# 05_MCU.net
KiCad netlist of a schematic drawn in Altium Designer
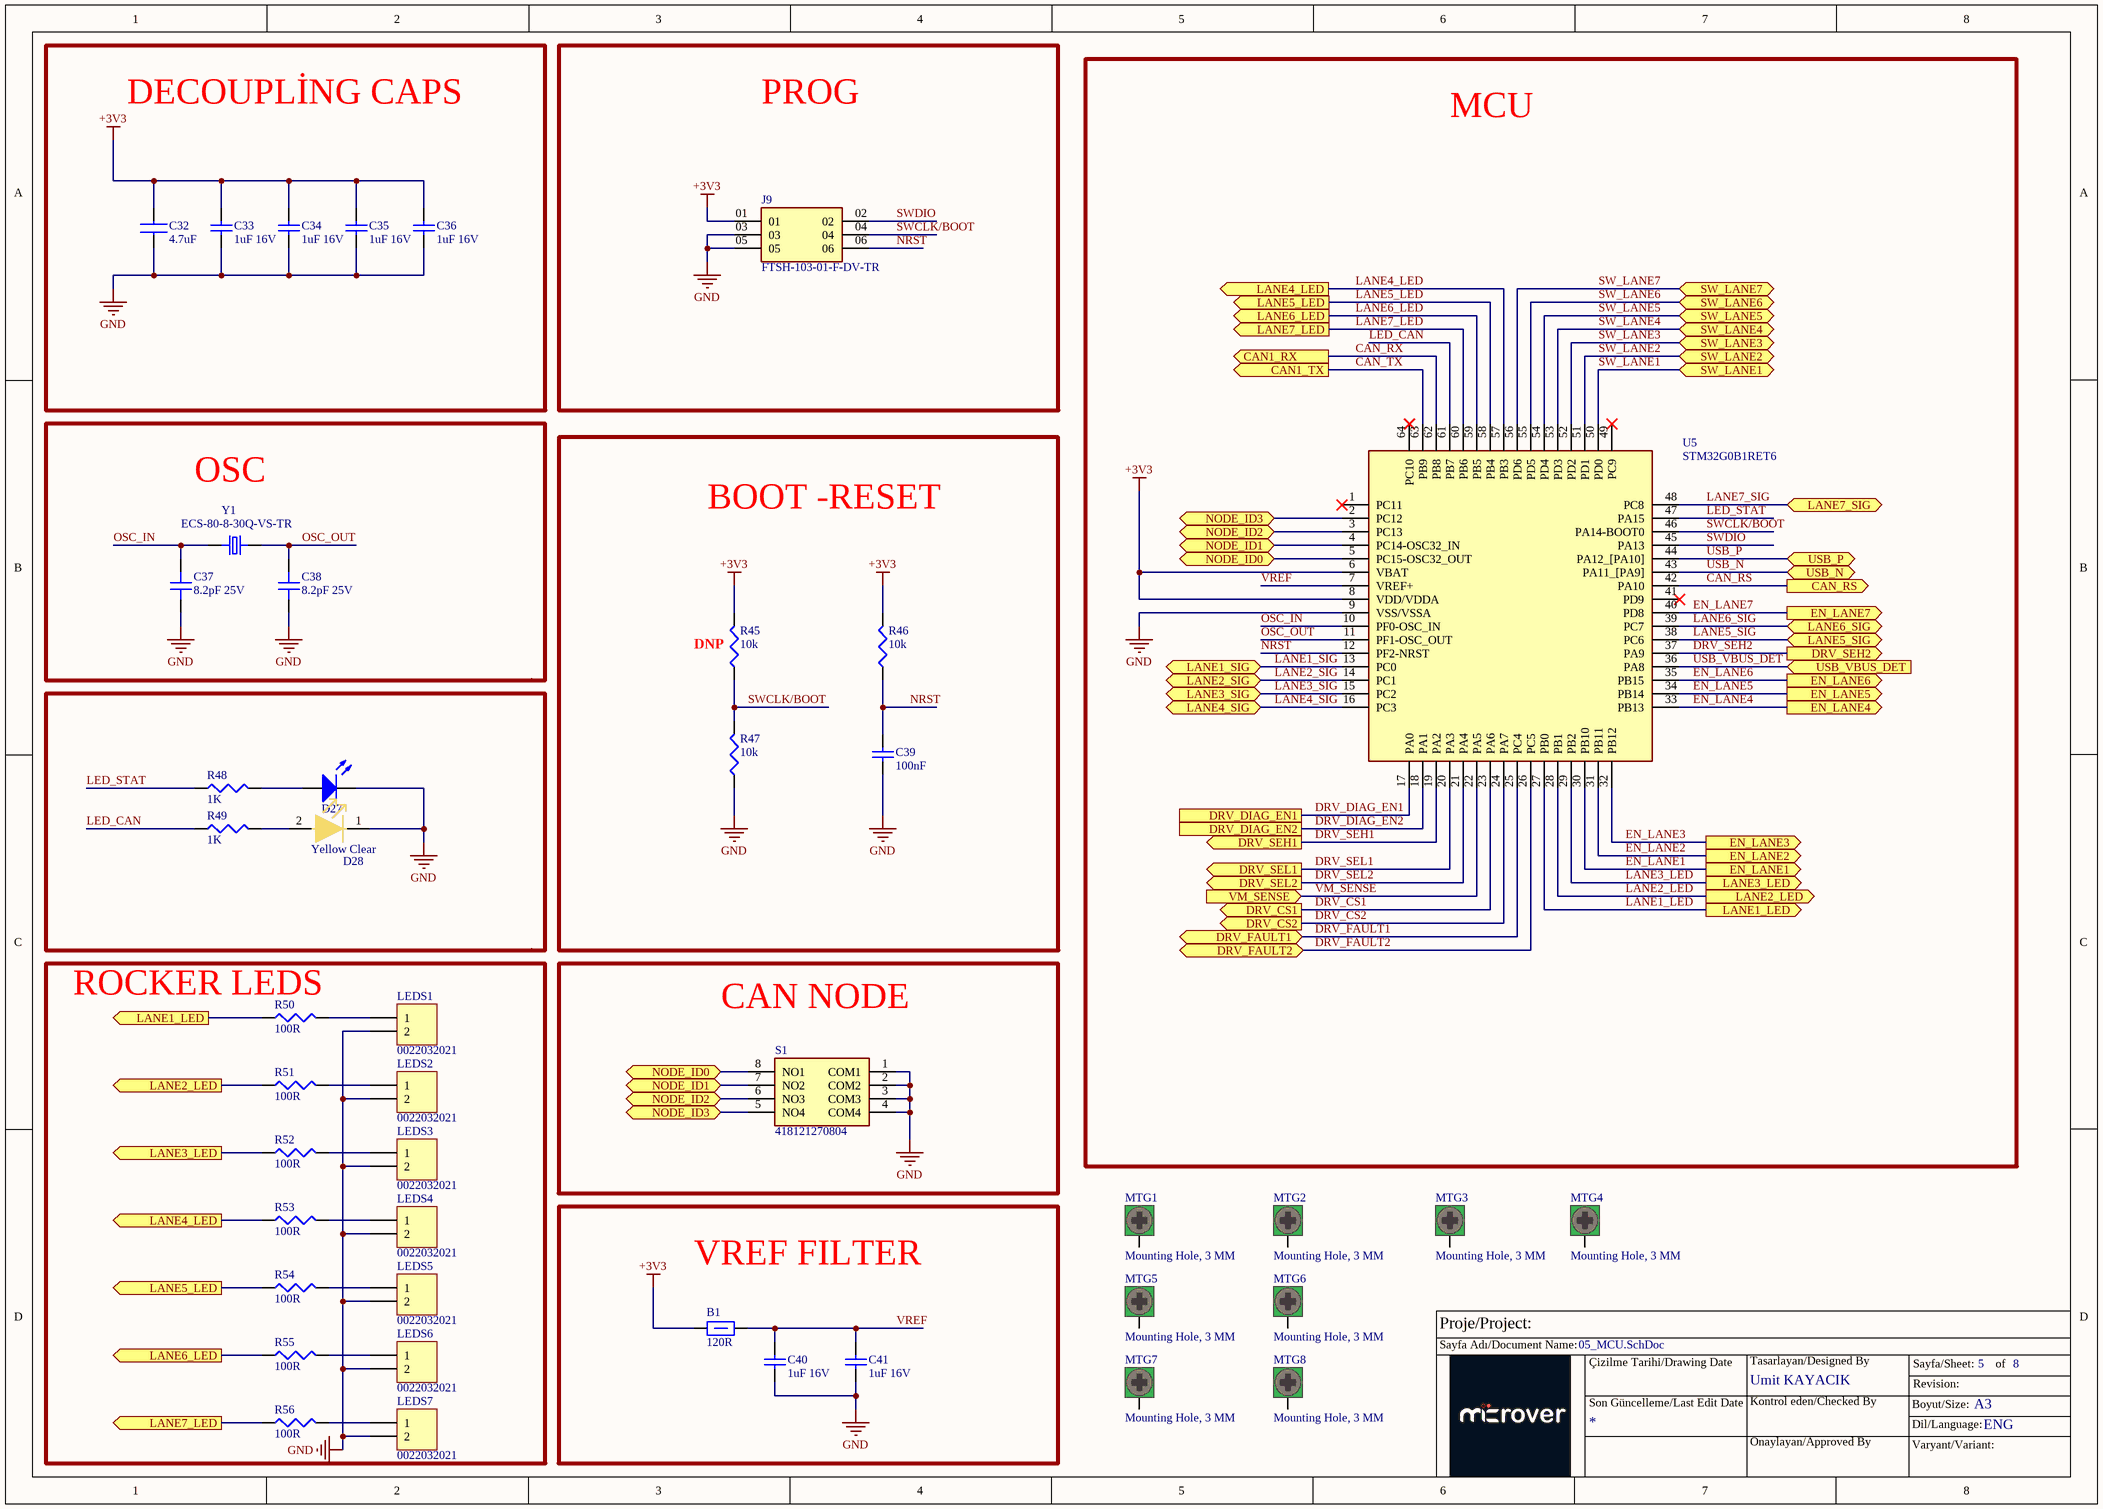
[diagram p0: 05_MCU.SchDoc]

(export (version "E")
  (design (tool "Eeschema 10.0.6"))
  (components
    (comp (ref "B1")
      (value "120R")
      (footprint "F0603")
      (description "BEAD FERRITE 120R 1LN SMD 0603")
      (fields (field (name "MANUFACTURER") "MURATA"))
      (libsource (lib "HW_ADHERENT_LANECTRL_R1") (part "BEAD FERRITE 120R 1LN SMD 0603"))
    )
    (comp (ref "C32")
      (value "4.7uF")
      (footprint "CAP0603")
      (description "4.7 µF ±20% 10V Ceramic Capacitor X5R 0603 (1608 Metric)")
      (fields (field (name "MANUFACTURER PART NUMBER") "GRM185R61A475ME11D"))
      (libsource (lib "HW_ADHERENT_LANECTRL_R1") (part "CAP0603_4.7uF_10V"))
    )
    (comp (ref "C33")
      (value "1uF 16V")
      (footprint "SMC0603")
      (description "1 µF ±10% 16V Ceramic Capacitor X7R 0603 (1608 Metric)")
      (fields
        (field (name "MANUFACTURER PART NUMBER") "CGA3E1X7R1C105K080AC")
        (field (name "Comment") "CAP CER 1UF 16V X7R 0603")
      )
      (libsource (lib "HW_ADHERENT_LANECTRL_R1") (part "CAP0603_1UF_16V"))
    )
    (comp (ref "C34")
      (value "1uF 16V")
      (footprint "SMC0603")
      (description "1 µF ±10% 16V Ceramic Capacitor X7R 0603 (1608 Metric)")
      (fields
        (field (name "MANUFACTURER PART NUMBER") "CGA3E1X7R1C105K080AC")
        (field (name "Comment") "CAP CER 1UF 16V X7R 0603")
      )
      (libsource (lib "HW_ADHERENT_LANECTRL_R1") (part "CAP0603_1UF_16V"))
    )
    (comp (ref "C35")
      (value "1uF 16V")
      (footprint "SMC0603")
      (description "1 µF ±10% 16V Ceramic Capacitor X7R 0603 (1608 Metric)")
      (fields
        (field (name "MANUFACTURER PART NUMBER") "CGA3E1X7R1C105K080AC")
        (field (name "Comment") "CAP CER 1UF 16V X7R 0603")
      )
      (libsource (lib "HW_ADHERENT_LANECTRL_R1") (part "CAP0603_1UF_16V"))
    )
    (comp (ref "C36")
      (value "1uF 16V")
      (footprint "SMC0603")
      (description "1 µF ±10% 16V Ceramic Capacitor X7R 0603 (1608 Metric)")
      (fields
        (field (name "MANUFACTURER PART NUMBER") "CGA3E1X7R1C105K080AC")
        (field (name "Comment") "CAP CER 1UF 16V X7R 0603")
      )
      (libsource (lib "HW_ADHERENT_LANECTRL_R1") (part "CAP0603_1UF_16V"))
    )
    (comp (ref "C37")
      (value "8.2pF 25V")
      (footprint "0402_C")
      (description "CAP0402 COG 8.2PF 5% 25V")
      (libsource (lib "HW_ADHERENT_LANECTRL_R1") (part "GMC04CG8R2J25NT"))
    )
    (comp (ref "C38")
      (value "8.2pF 25V")
      (footprint "0402_C")
      (description "CAP0402 COG 8.2PF 5% 25V")
      (libsource (lib "HW_ADHERENT_LANECTRL_R1") (part "GMC04CG8R2J25NT"))
    )
    (comp (ref "C39")
      (value "100nF")
      (footprint "CAP0603")
      (description "0.1 µF ±10% 50V Ceramic Capacitor X7R 0603 (1608 Metric)")
      (fields
        (field (name "MANUFACTURER PART NUMBER") "CL10B104KA8NNNC")
        (field (name "LCSC PART NUMBER") "C1590")
      )
      (libsource (lib "HW_ADHERENT_LANECTRL_R1") (part "CAP0603_100nF"))
    )
    (comp (ref "C40")
      (value "1uF 16V")
      (footprint "SMC0603")
      (description "1 µF ±10% 16V Ceramic Capacitor X7R 0603 (1608 Metric)")
      (fields
        (field (name "MANUFACTURER PART NUMBER") "CGA3E1X7R1C105K080AC")
        (field (name "Comment") "CAP CER 1UF 16V X7R 0603")
      )
      (libsource (lib "HW_ADHERENT_LANECTRL_R1") (part "CAP0603_1UF_16V"))
    )
    (comp (ref "C41")
      (value "1uF 16V")
      (footprint "SMC0603")
      (description "1 µF ±10% 16V Ceramic Capacitor X7R 0603 (1608 Metric)")
      (fields
        (field (name "MANUFACTURER PART NUMBER") "CGA3E1X7R1C105K080AC")
        (field (name "Comment") "CAP CER 1UF 16V X7R 0603")
      )
      (libsource (lib "HW_ADHERENT_LANECTRL_R1") (part "CAP0603_1UF_16V"))
    )
    (comp (ref "D27")
      (value "LED GREEN")
      (footprint "LED0805")
      (description "Green 570nm LED Indication - Discrete 2.1V 0805 (2012 Metric)")
      (fields
        (field (name "MANUFACTURER PART NUMBER") "QTLP630C4TR")
        (field (name "MANUFACTURER") "Everlight Electronics Co Ltd")
      )
      (libsource (lib "HW_ADHERENT_LANECTRL_R1") (part "LED0805_GREEN"))
    )
    (comp (ref "D28")
      (value "LED YELLOW CLEAR SMD")
      (footprint "Lite-On_Yellow_0603")
      (description "Yellow 591nm LED Indication - Discrete 2.1V 0603 (1608 Metric)")
      (fields (field (name "MANUFACTURER PART NUMBER") "LTST-C191KSKT") (field (name "COLOR") "Yellow Clear"))
      (libsource (lib "HW_ADHERENT_LANECTRL_R1") (part "LTST-C191KSKT"))
    )
    (comp (ref "J9")
      (value "FTSH-103-01-F-DV-TR")
      (footprint "SAMTEC_FTSH-103-01-F-DV-TR")
      (description "Connector Header Surface Mount 6 position 0.050\" (1.27mm)")
      (fields (field (name "MANUFACTURER") "Samtec Inc."))
      (libsource (lib "HW_ADHERENT_LANECTRL_R1") (part "FTSH-103-01-F-DV-TR"))
    )
    (comp (ref "LEDS1")
      (value "0022032021")
      (footprint "THD 1x2p. male straight")
      (description "CONN HEADER VERT 2POS 2.54MM")
      (fields (field (name "MANUFACTURER") "Molex"))
      (libsource (lib "HW_ADHERENT_LANECTRL_R1") (part "Header 2"))
    )
    (comp (ref "LEDS2")
      (value "0022032021")
      (footprint "THD 1x2p. male straight")
      (description "CONN HEADER VERT 2POS 2.54MM")
      (fields (field (name "MANUFACTURER") "Molex"))
      (libsource (lib "HW_ADHERENT_LANECTRL_R1") (part "Header 2"))
    )
    (comp (ref "LEDS3")
      (value "0022032021")
      (footprint "THD 1x2p. male straight")
      (description "CONN HEADER VERT 2POS 2.54MM")
      (fields (field (name "MANUFACTURER") "Molex"))
      (libsource (lib "HW_ADHERENT_LANECTRL_R1") (part "Header 2"))
    )
    (comp (ref "LEDS4")
      (value "0022032021")
      (footprint "THD 1x2p. male straight")
      (description "CONN HEADER VERT 2POS 2.54MM")
      (fields (field (name "MANUFACTURER") "Molex"))
      (libsource (lib "HW_ADHERENT_LANECTRL_R1") (part "Header 2"))
    )
    (comp (ref "LEDS5")
      (value "0022032021")
      (footprint "THD 1x2p. male straight")
      (description "CONN HEADER VERT 2POS 2.54MM")
      (fields (field (name "MANUFACTURER") "Molex"))
      (libsource (lib "HW_ADHERENT_LANECTRL_R1") (part "Header 2"))
    )
    (comp (ref "LEDS6")
      (value "0022032021")
      (footprint "THD 1x2p. male straight")
      (description "CONN HEADER VERT 2POS 2.54MM")
      (fields (field (name "MANUFACTURER") "Molex"))
      (libsource (lib "HW_ADHERENT_LANECTRL_R1") (part "Header 2"))
    )
    (comp (ref "LEDS7")
      (value "0022032021")
      (footprint "THD 1x2p. male straight")
      (description "CONN HEADER VERT 2POS 2.54MM")
      (fields (field (name "MANUFACTURER") "Molex"))
      (libsource (lib "HW_ADHERENT_LANECTRL_R1") (part "Header 2"))
    )
    (comp (ref "MTG1")
      (value "Mounting Hole, 3 MM")
      (footprint "M3 Mounting Hole")
      (libsource (lib "HW_ADHERENT_LANECTRL_R1") (part "MTG3MM_8"))
    )
    (comp (ref "MTG2")
      (value "Mounting Hole, 3 MM")
      (footprint "M3 Mounting Hole")
      (libsource (lib "HW_ADHERENT_LANECTRL_R1") (part "MTG3MM_8"))
    )
    (comp (ref "MTG3")
      (value "Mounting Hole, 3 MM")
      (footprint "M3 Mounting Hole")
      (libsource (lib "HW_ADHERENT_LANECTRL_R1") (part "MTG3MM_8"))
    )
    (comp (ref "MTG4")
      (value "Mounting Hole, 3 MM")
      (footprint "M3 Mounting Hole")
      (libsource (lib "HW_ADHERENT_LANECTRL_R1") (part "MTG3MM_8"))
    )
    (comp (ref "MTG5")
      (value "Mounting Hole, 3 MM")
      (footprint "M3 Mounting Hole")
      (libsource (lib "HW_ADHERENT_LANECTRL_R1") (part "MTG3MM_8"))
    )
    (comp (ref "MTG6")
      (value "Mounting Hole, 3 MM")
      (footprint "M3 Mounting Hole")
      (libsource (lib "HW_ADHERENT_LANECTRL_R1") (part "MTG3MM_8"))
    )
    (comp (ref "MTG7")
      (value "Mounting Hole, 3 MM")
      (footprint "M3 Mounting Hole")
      (libsource (lib "HW_ADHERENT_LANECTRL_R1") (part "MTG3MM_8"))
    )
    (comp (ref "MTG8")
      (value "Mounting Hole, 3 MM")
      (footprint "M3 Mounting Hole")
      (libsource (lib "HW_ADHERENT_LANECTRL_R1") (part "MTG3MM_8"))
    )
    (comp (ref "R45")
      (value "10k")
      (footprint "SMR0603")
      (description "10 kOhms ±1% 0.1W, 1/10W Chip Resistor 0603 (1608 Metric) Moisture Resistant Thick Film")
      (fields
        (field (name "MANUFACTURER PART NUMBER") "RC0603FR-0710KL")
        (field (name "LCSC PART NUMBER") "C98220")
      )
      (libsource (lib "HW_ADHERENT_LANECTRL_R1") (part "RES0603_10K_%1"))
    )
    (comp (ref "R46")
      (value "10k")
      (footprint "SMR0603")
      (description "10 kOhms ±1% 0.1W, 1/10W Chip Resistor 0603 (1608 Metric) Moisture Resistant Thick Film")
      (fields
        (field (name "MANUFACTURER PART NUMBER") "RC0603FR-0710KL")
        (field (name "LCSC PART NUMBER") "C98220")
      )
      (libsource (lib "HW_ADHERENT_LANECTRL_R1") (part "RES0603_10K_%1"))
    )
    (comp (ref "R47")
      (value "10k")
      (footprint "SMR0603")
      (description "10 kOhms ±1% 0.1W, 1/10W Chip Resistor 0603 (1608 Metric) Moisture Resistant Thick Film")
      (fields
        (field (name "MANUFACTURER PART NUMBER") "RC0603FR-0710KL")
        (field (name "LCSC PART NUMBER") "C98220")
      )
      (libsource (lib "HW_ADHERENT_LANECTRL_R1") (part "RES0603_10K_%1"))
    )
    (comp (ref "R48")
      (value "1K")
      (footprint "R 0603(1608)")
      (description "RES SMD 1K OHM 1% 1/10W 0603")
      (fields
        (field (name "MANUFACTURER") "Yageo")
        (field (name "MANUFACTURER PART NUMBER") "RC0603FR-071KL")
      )
      (libsource (lib "HW_ADHERENT_LANECTRL_R1") (part "Res3_9"))
    )
    (comp (ref "R49")
      (value "1K")
      (footprint "R 0603(1608)")
      (description "RES SMD 1K OHM 1% 1/10W 0603")
      (fields
        (field (name "MANUFACTURER") "Yageo")
        (field (name "MANUFACTURER PART NUMBER") "RC0603FR-071KL")
      )
      (libsource (lib "HW_ADHERENT_LANECTRL_R1") (part "Res3_9"))
    )
    (comp (ref "R50")
      (value "100R")
      (footprint "SMR0603")
      (description "100 Ohms ±1% 0.1W, 1/10W Chip Resistor 0603 (1608 Metric) Moisture Resistant Thick Film")
      (fields
        (field (name "MANUFACTURER PART NUMBER") "RC0603FR-07100RL")
        (field (name "LCSC PART NUMBER") "C105588")
      )
      (libsource (lib "HW_ADHERENT_LANECTRL_R1") (part "RES0603_100R_%1_1"))
    )
    (comp (ref "R51")
      (value "100R")
      (footprint "SMR0603")
      (description "100 Ohms ±1% 0.1W, 1/10W Chip Resistor 0603 (1608 Metric) Moisture Resistant Thick Film")
      (fields
        (field (name "MANUFACTURER PART NUMBER") "RC0603FR-07100RL")
        (field (name "LCSC PART NUMBER") "C105588")
      )
      (libsource (lib "HW_ADHERENT_LANECTRL_R1") (part "RES0603_100R_%1_1"))
    )
    (comp (ref "R52")
      (value "100R")
      (footprint "SMR0603")
      (description "100 Ohms ±1% 0.1W, 1/10W Chip Resistor 0603 (1608 Metric) Moisture Resistant Thick Film")
      (fields
        (field (name "MANUFACTURER PART NUMBER") "RC0603FR-07100RL")
        (field (name "LCSC PART NUMBER") "C105588")
      )
      (libsource (lib "HW_ADHERENT_LANECTRL_R1") (part "RES0603_100R_%1_1"))
    )
    (comp (ref "R53")
      (value "100R")
      (footprint "SMR0603")
      (description "100 Ohms ±1% 0.1W, 1/10W Chip Resistor 0603 (1608 Metric) Moisture Resistant Thick Film")
      (fields
        (field (name "MANUFACTURER PART NUMBER") "RC0603FR-07100RL")
        (field (name "LCSC PART NUMBER") "C105588")
      )
      (libsource (lib "HW_ADHERENT_LANECTRL_R1") (part "RES0603_100R_%1_1"))
    )
    (comp (ref "R54")
      (value "100R")
      (footprint "SMR0603")
      (description "100 Ohms ±1% 0.1W, 1/10W Chip Resistor 0603 (1608 Metric) Moisture Resistant Thick Film")
      (fields
        (field (name "MANUFACTURER PART NUMBER") "RC0603FR-07100RL")
        (field (name "LCSC PART NUMBER") "C105588")
      )
      (libsource (lib "HW_ADHERENT_LANECTRL_R1") (part "RES0603_100R_%1_1"))
    )
    (comp (ref "R55")
      (value "100R")
      (footprint "SMR0603")
      (description "100 Ohms ±1% 0.1W, 1/10W Chip Resistor 0603 (1608 Metric) Moisture Resistant Thick Film")
      (fields
        (field (name "MANUFACTURER PART NUMBER") "RC0603FR-07100RL")
        (field (name "LCSC PART NUMBER") "C105588")
      )
      (libsource (lib "HW_ADHERENT_LANECTRL_R1") (part "RES0603_100R_%1_1"))
    )
    (comp (ref "R56")
      (value "100R")
      (footprint "SMR0603")
      (description "100 Ohms ±1% 0.1W, 1/10W Chip Resistor 0603 (1608 Metric) Moisture Resistant Thick Film")
      (fields
        (field (name "MANUFACTURER PART NUMBER") "RC0603FR-07100RL")
        (field (name "LCSC PART NUMBER") "C105588")
      )
      (libsource (lib "HW_ADHERENT_LANECTRL_R1") (part "RES0603_100R_%1_1"))
    )
    (comp (ref "S1")
      (value "418121270804")
      (footprint "418121270804")
      (description "Dip Switch, 0.025A, 24Vdc, 4 Pos, Smd Rohs Compliant: Yes ¦Wurth Elektronik 418121270804")
      (fields (field (name "MANUFACTURER") "Wurth Electronics"))
      (libsource (lib "HW_ADHERENT_LANECTRL_R1") (part "418121270804"))
    )
    (comp (ref "U5")
      (value "STM32G0B1RET6")
      (footprint "QFP50P1200X1200X160-64N")
      (description "ARM® Cortex®-M0+ STM32G0 Microcontroller IC 32-Bit 64MHz 512KB (512K x 8) FLASH 64-LQFP (10x10)")
      (libsource (lib "HW_ADHERENT_LANECTRL_R1") (part "STM32G0B1RET6"))
    )
    (comp (ref "Y1")
      (value "ECS-80-8-30Q-VS-TR")
      (footprint "XTAL_ECS-80-8-30Q-VS-TR")
      (description "CRYSTAL 8.0000MHZ 8PF SMD")
      (fields (field (name "MANUFACTURER") "ESC Inc."))
      (libsource (lib "HW_ADHERENT_LANECTRL_R1") (part "ECS-80-8-30Q-VS-TR"))
    )
  )
  (nets
    (net (code "1") (name "+3V3") (class "Default")
      (node (ref "B1") (pin "1") (pinfunction "1_1") (pintype "passive"))
      (node (ref "C32") (pin "2") (pinfunction "2_2") (pintype "passive"))
      (node (ref "C33") (pin "2") (pinfunction "2_2") (pintype "passive"))
      (node (ref "C34") (pin "2") (pinfunction "2_2") (pintype "passive"))
      (node (ref "C35") (pin "2") (pinfunction "2_2") (pintype "passive"))
      (node (ref "C36") (pin "2") (pinfunction "2_2") (pintype "passive"))
      (node (ref "J9") (pin "01") (pinfunction "01_01") (pintype "passive"))
      (node (ref "R45") (pin "2") (pinfunction "2_2") (pintype "passive"))
      (node (ref "R46") (pin "2") (pinfunction "2_2") (pintype "passive"))
      (node (ref "U5") (pin "6") (pinfunction "VBAT_6") (pintype "passive"))
      (node (ref "U5") (pin "8") (pinfunction "VDD/VDDA_8") (pintype "passive"))
    )
    (net (code "2") (name "/CAN_RS") (class "Default")
      (node (ref "U5") (pin "42") (pinfunction "PA10_42") (pintype "passive"))
    )
    (net (code "3") (name "/CAN_RX") (class "Default")
      (node (ref "U5") (pin "62") (pinfunction "PB8_62") (pintype "passive"))
    )
    (net (code "4") (name "/CAN_TX") (class "Default")
      (node (ref "U5") (pin "63") (pinfunction "PB9_63") (pintype "passive"))
    )
    (net (code "5") (name "/DRV_CS1") (class "Default")
      (node (ref "U5") (pin "23") (pinfunction "PA6_23") (pintype "passive"))
    )
    (net (code "6") (name "/DRV_CS2") (class "Default")
      (node (ref "U5") (pin "24") (pinfunction "PA7_24") (pintype "passive"))
    )
    (net (code "7") (name "/DRV_DIAG_EN1") (class "Default")
      (node (ref "U5") (pin "17") (pinfunction "PA0_17") (pintype "passive"))
    )
    (net (code "8") (name "/DRV_DIAG_EN2") (class "Default")
      (node (ref "U5") (pin "18") (pinfunction "PA1_18") (pintype "passive"))
    )
    (net (code "9") (name "/DRV_FAULT1") (class "Default")
      (node (ref "U5") (pin "25") (pinfunction "PC4_25") (pintype "passive"))
    )
    (net (code "10") (name "/DRV_FAULT2") (class "Default")
      (node (ref "U5") (pin "26") (pinfunction "PC5_26") (pintype "passive"))
    )
    (net (code "11") (name "/DRV_SEH1") (class "Default")
      (node (ref "U5") (pin "19") (pinfunction "PA2_19") (pintype "passive"))
    )
    (net (code "12") (name "/DRV_SEH2") (class "Default")
      (node (ref "U5") (pin "37") (pinfunction "PA9_37") (pintype "passive"))
    )
    (net (code "13") (name "/DRV_SEL1") (class "Default")
      (node (ref "U5") (pin "20") (pinfunction "PA3_20") (pintype "passive"))
    )
    (net (code "14") (name "/DRV_SEL2") (class "Default")
      (node (ref "U5") (pin "21") (pinfunction "PA4_21") (pintype "passive"))
    )
    (net (code "15") (name "/EN_LANE1") (class "Default")
      (node (ref "U5") (pin "30") (pinfunction "PB10_30") (pintype "passive"))
    )
    (net (code "16") (name "/EN_LANE2") (class "Default")
      (node (ref "U5") (pin "31") (pinfunction "PB11_31") (pintype "passive"))
    )
    (net (code "17") (name "/EN_LANE3") (class "Default")
      (node (ref "U5") (pin "32") (pinfunction "PB12_32") (pintype "passive"))
    )
    (net (code "18") (name "/EN_LANE4") (class "Default")
      (node (ref "U5") (pin "33") (pinfunction "PB13_33") (pintype "passive"))
    )
    (net (code "19") (name "/EN_LANE5") (class "Default")
      (node (ref "U5") (pin "34") (pinfunction "PB14_34") (pintype "passive"))
    )
    (net (code "20") (name "/EN_LANE6") (class "Default")
      (node (ref "U5") (pin "35") (pinfunction "PB15_35") (pintype "passive"))
    )
    (net (code "21") (name "/EN_LANE7") (class "Default")
      (node (ref "U5") (pin "40") (pinfunction "PD8_40") (pintype "passive"))
    )
    (net (code "22") (name "/LANE1_LED") (class "Default")
      (node (ref "R50") (pin "1") (pinfunction "1_1") (pintype "passive"))
      (node (ref "U5") (pin "27") (pinfunction "PB0_27") (pintype "passive"))
    )
    (net (code "23") (name "/LANE1_SIG") (class "Default")
      (node (ref "U5") (pin "13") (pinfunction "PC0_13") (pintype "passive"))
    )
    (net (code "24") (name "/LANE2_LED") (class "Default")
      (node (ref "R51") (pin "1") (pinfunction "1_1") (pintype "passive"))
      (node (ref "U5") (pin "28") (pinfunction "PB1_28") (pintype "passive"))
    )
    (net (code "25") (name "/LANE2_SIG") (class "Default")
      (node (ref "U5") (pin "14") (pinfunction "PC1_14") (pintype "passive"))
    )
    (net (code "26") (name "/LANE3_LED") (class "Default")
      (node (ref "R52") (pin "1") (pinfunction "1_1") (pintype "passive"))
      (node (ref "U5") (pin "29") (pinfunction "PB2_29") (pintype "passive"))
    )
    (net (code "27") (name "/LANE3_SIG") (class "Default")
      (node (ref "U5") (pin "15") (pinfunction "PC2_15") (pintype "passive"))
    )
    (net (code "28") (name "/LANE4_LED") (class "Default")
      (node (ref "R53") (pin "1") (pinfunction "1_1") (pintype "passive"))
      (node (ref "U5") (pin "57") (pinfunction "PB3_57") (pintype "passive"))
    )
    (net (code "29") (name "/LANE4_SIG") (class "Default")
      (node (ref "U5") (pin "16") (pinfunction "PC3_16") (pintype "passive"))
    )
    (net (code "30") (name "/LANE5_LED") (class "Default")
      (node (ref "R54") (pin "1") (pinfunction "1_1") (pintype "passive"))
      (node (ref "U5") (pin "58") (pinfunction "PB4_58") (pintype "passive"))
    )
    (net (code "31") (name "/LANE5_SIG") (class "Default")
      (node (ref "U5") (pin "38") (pinfunction "PC6_38") (pintype "passive"))
    )
    (net (code "32") (name "/LANE6_LED") (class "Default")
      (node (ref "R55") (pin "1") (pinfunction "1_1") (pintype "passive"))
      (node (ref "U5") (pin "59") (pinfunction "PB5_59") (pintype "passive"))
    )
    (net (code "33") (name "/LANE6_SIG") (class "Default")
      (node (ref "U5") (pin "39") (pinfunction "PC7_39") (pintype "passive"))
    )
    (net (code "34") (name "/LANE7_LED") (class "Default")
      (node (ref "R56") (pin "1") (pinfunction "1_1") (pintype "passive"))
      (node (ref "U5") (pin "60") (pinfunction "PB6_60") (pintype "passive"))
    )
    (net (code "35") (name "/LANE7_SIG") (class "Default")
      (node (ref "U5") (pin "48") (pinfunction "PC8_48") (pintype "passive"))
    )
    (net (code "36") (name "/LED_CAN") (class "Default")
      (node (ref "R49") (pin "1") (pinfunction "1_1") (pintype "passive"))
      (node (ref "U5") (pin "61") (pinfunction "PB7_61") (pintype "passive"))
    )
    (net (code "37") (name "/LED_STAT") (class "Default")
      (node (ref "R48") (pin "1") (pinfunction "1_1") (pintype "passive"))
      (node (ref "U5") (pin "47") (pinfunction "PA15_47") (pintype "passive"))
    )
    (net (code "38") (name "/NODE_ID0") (class "Default")
      (node (ref "S1") (pin "8") (pinfunction "NO1_8") (pintype "passive"))
      (node (ref "U5") (pin "5") (pinfunction "PC15-OSC32_OUT_5") (pintype "passive"))
    )
    (net (code "39") (name "/NODE_ID1") (class "Default")
      (node (ref "S1") (pin "7") (pinfunction "NO2_7") (pintype "passive"))
      (node (ref "U5") (pin "4") (pinfunction "PC14-OSC32_IN_4") (pintype "passive"))
    )
    (net (code "40") (name "/NODE_ID2") (class "Default")
      (node (ref "S1") (pin "6") (pinfunction "NO3_6") (pintype "passive"))
      (node (ref "U5") (pin "3") (pinfunction "PC13_3") (pintype "passive"))
    )
    (net (code "41") (name "/NODE_ID3") (class "Default")
      (node (ref "S1") (pin "5") (pinfunction "NO4_5") (pintype "passive"))
      (node (ref "U5") (pin "2") (pinfunction "PC12_2") (pintype "passive"))
    )
    (net (code "42") (name "/NRST") (class "Default")
      (node (ref "C39") (pin "2") (pinfunction "2_2") (pintype "passive"))
      (node (ref "J9") (pin "06") (pinfunction "06_06") (pintype "passive"))
      (node (ref "R46") (pin "1") (pinfunction "1_1") (pintype "passive"))
      (node (ref "U5") (pin "12") (pinfunction "PF2-NRST_12") (pintype "passive"))
    )
    (net (code "43") (name "/OSC_IN") (class "Default")
      (node (ref "C37") (pin "2") (pinfunction "2_2") (pintype "passive"))
      (node (ref "U5") (pin "10") (pinfunction "PF0-OSC_IN_10") (pintype "passive"))
      (node (ref "Y1") (pin "1") (pinfunction "IN/OUT_1") (pintype "passive"))
    )
    (net (code "44") (name "/OSC_OUT") (class "Default")
      (node (ref "C38") (pin "2") (pinfunction "2_2") (pintype "passive"))
      (node (ref "U5") (pin "11") (pinfunction "PF1-OSC_OUT_11") (pintype "passive"))
      (node (ref "Y1") (pin "2") (pinfunction "OUT/IN_2") (pintype "passive"))
    )
    (net (code "45") (name "/SWCLK{slash}BOOT") (class "Default")
      (node (ref "J9") (pin "04") (pinfunction "04_04") (pintype "passive"))
      (node (ref "R45") (pin "1") (pinfunction "1_1") (pintype "passive"))
      (node (ref "R47") (pin "2") (pinfunction "2_2") (pintype "passive"))
      (node (ref "U5") (pin "46") (pinfunction "PA14-BOOT0_46") (pintype "passive"))
    )
    (net (code "46") (name "/SWDIO") (class "Default")
      (node (ref "J9") (pin "02") (pinfunction "02_02") (pintype "passive"))
      (node (ref "U5") (pin "45") (pinfunction "PA13_45") (pintype "passive"))
    )
    (net (code "47") (name "/SW_LANE1") (class "Default")
      (node (ref "U5") (pin "50") (pinfunction "PD0_50") (pintype "passive"))
    )
    (net (code "48") (name "/SW_LANE2") (class "Default")
      (node (ref "U5") (pin "51") (pinfunction "PD1_51") (pintype "passive"))
    )
    (net (code "49") (name "/SW_LANE3") (class "Default")
      (node (ref "U5") (pin "52") (pinfunction "PD2_52") (pintype "passive"))
    )
    (net (code "50") (name "/SW_LANE4") (class "Default")
      (node (ref "U5") (pin "53") (pinfunction "PD3_53") (pintype "passive"))
    )
    (net (code "51") (name "/SW_LANE5") (class "Default")
      (node (ref "U5") (pin "54") (pinfunction "PD4_54") (pintype "passive"))
    )
    (net (code "52") (name "/SW_LANE6") (class "Default")
      (node (ref "U5") (pin "55") (pinfunction "PD5_55") (pintype "passive"))
    )
    (net (code "53") (name "/SW_LANE7") (class "Default")
      (node (ref "U5") (pin "56") (pinfunction "PD6_56") (pintype "passive"))
    )
    (net (code "54") (name "/USB_N") (class "Default")
      (node (ref "U5") (pin "43") (pinfunction "PA11_[PA9]_43") (pintype "passive"))
    )
    (net (code "55") (name "/USB_P") (class "Default")
      (node (ref "U5") (pin "44") (pinfunction "PA12_[PA10]_44") (pintype "passive"))
    )
    (net (code "56") (name "/USB_VBUS_DET") (class "Default")
      (node (ref "U5") (pin "36") (pinfunction "PA8_36") (pintype "passive"))
    )
    (net (code "57") (name "/VM_SENSE") (class "Default")
      (node (ref "U5") (pin "22") (pinfunction "PA5_22") (pintype "passive"))
    )
    (net (code "58") (name "/VREF") (class "Default")
      (node (ref "B1") (pin "2") (pinfunction "2_2") (pintype "passive"))
      (node (ref "C40") (pin "2") (pinfunction "2_2") (pintype "passive"))
      (node (ref "C41") (pin "2") (pinfunction "2_2") (pintype "passive"))
      (node (ref "U5") (pin "7") (pinfunction "VREF+_7") (pintype "passive"))
    )
    (net (code "59") (name "GND") (class "Default")
      (node (ref "C32") (pin "1") (pinfunction "1_1") (pintype "passive"))
      (node (ref "C33") (pin "1") (pinfunction "1_1") (pintype "passive"))
      (node (ref "C34") (pin "1") (pinfunction "1_1") (pintype "passive"))
      (node (ref "C35") (pin "1") (pinfunction "1_1") (pintype "passive"))
      (node (ref "C36") (pin "1") (pinfunction "1_1") (pintype "passive"))
      (node (ref "C37") (pin "1") (pinfunction "1_1") (pintype "passive"))
      (node (ref "C38") (pin "1") (pinfunction "1_1") (pintype "passive"))
      (node (ref "C39") (pin "1") (pinfunction "1_1") (pintype "passive"))
      (node (ref "C40") (pin "1") (pinfunction "1_1") (pintype "passive"))
      (node (ref "C41") (pin "1") (pinfunction "1_1") (pintype "passive"))
      (node (ref "D27") (pin "1") (pinfunction "K_1") (pintype "passive"))
      (node (ref "D28") (pin "1") (pinfunction "C_1") (pintype "passive"))
      (node (ref "J9") (pin "03") (pinfunction "03_03") (pintype "passive"))
      (node (ref "J9") (pin "05") (pinfunction "05_05") (pintype "passive"))
      (node (ref "LEDS1") (pin "2") (pinfunction "2_2") (pintype "passive"))
      (node (ref "LEDS2") (pin "2") (pinfunction "2_2") (pintype "passive"))
      (node (ref "LEDS3") (pin "2") (pinfunction "2_2") (pintype "passive"))
      (node (ref "LEDS4") (pin "2") (pinfunction "2_2") (pintype "passive"))
      (node (ref "LEDS5") (pin "2") (pinfunction "2_2") (pintype "passive"))
      (node (ref "LEDS6") (pin "2") (pinfunction "2_2") (pintype "passive"))
      (node (ref "LEDS7") (pin "2") (pinfunction "2_2") (pintype "passive"))
      (node (ref "R47") (pin "1") (pinfunction "1_1") (pintype "passive"))
      (node (ref "S1") (pin "1") (pinfunction "COM1_1") (pintype "passive"))
      (node (ref "S1") (pin "2") (pinfunction "COM2_2") (pintype "passive"))
      (node (ref "S1") (pin "3") (pinfunction "COM3_3") (pintype "passive"))
      (node (ref "S1") (pin "4") (pinfunction "COM4_4") (pintype "passive"))
      (node (ref "U5") (pin "9") (pinfunction "VSS/VSSA_9") (pintype "passive"))
    )
    (net (code "60") (name "Net-(D27-A)") (class "Default")
      (node (ref "D27") (pin "2") (pinfunction "A_2") (pintype "passive"))
      (node (ref "R48") (pin "2") (pinfunction "2_2") (pintype "passive"))
    )
    (net (code "61") (name "Net-(D28-A)") (class "Default")
      (node (ref "D28") (pin "2") (pinfunction "A_2") (pintype "passive"))
      (node (ref "R49") (pin "2") (pinfunction "2_2") (pintype "passive"))
    )
    (net (code "62") (name "Net-(LEDS1-Pad1)") (class "Default")
      (node (ref "LEDS1") (pin "1") (pinfunction "1_1") (pintype "passive"))
      (node (ref "R50") (pin "2") (pinfunction "2_2") (pintype "passive"))
    )
    (net (code "63") (name "Net-(LEDS2-Pad1)") (class "Default")
      (node (ref "LEDS2") (pin "1") (pinfunction "1_1") (pintype "passive"))
      (node (ref "R51") (pin "2") (pinfunction "2_2") (pintype "passive"))
    )
    (net (code "64") (name "Net-(LEDS3-Pad1)") (class "Default")
      (node (ref "LEDS3") (pin "1") (pinfunction "1_1") (pintype "passive"))
      (node (ref "R52") (pin "2") (pinfunction "2_2") (pintype "passive"))
    )
    (net (code "65") (name "Net-(LEDS4-Pad1)") (class "Default")
      (node (ref "LEDS4") (pin "1") (pinfunction "1_1") (pintype "passive"))
      (node (ref "R53") (pin "2") (pinfunction "2_2") (pintype "passive"))
    )
    (net (code "66") (name "Net-(LEDS5-Pad1)") (class "Default")
      (node (ref "LEDS5") (pin "1") (pinfunction "1_1") (pintype "passive"))
      (node (ref "R54") (pin "2") (pinfunction "2_2") (pintype "passive"))
    )
    (net (code "67") (name "Net-(LEDS6-Pad1)") (class "Default")
      (node (ref "LEDS6") (pin "1") (pinfunction "1_1") (pintype "passive"))
      (node (ref "R55") (pin "2") (pinfunction "2_2") (pintype "passive"))
    )
    (net (code "68") (name "Net-(LEDS7-Pad1)") (class "Default")
      (node (ref "LEDS7") (pin "1") (pinfunction "1_1") (pintype "passive"))
      (node (ref "R56") (pin "2") (pinfunction "2_2") (pintype "passive"))
    )
    (net (code "69") (name "unconnected-(MTG1-Pad0)") (class "Default")
      (node (ref "MTG1") (pin "0") (pinfunction "0_0") (pintype "passive"))
    )
    (net (code "70") (name "unconnected-(MTG2-Pad0)") (class "Default")
      (node (ref "MTG2") (pin "0") (pinfunction "0_0") (pintype "passive"))
    )
    (net (code "71") (name "unconnected-(MTG3-Pad0)") (class "Default")
      (node (ref "MTG3") (pin "0") (pinfunction "0_0") (pintype "passive"))
    )
    (net (code "72") (name "unconnected-(MTG4-Pad0)") (class "Default")
      (node (ref "MTG4") (pin "0") (pinfunction "0_0") (pintype "passive"))
    )
    (net (code "73") (name "unconnected-(MTG5-Pad0)") (class "Default")
      (node (ref "MTG5") (pin "0") (pinfunction "0_0") (pintype "passive"))
    )
    (net (code "74") (name "unconnected-(MTG6-Pad0)") (class "Default")
      (node (ref "MTG6") (pin "0") (pinfunction "0_0") (pintype "passive"))
    )
    (net (code "75") (name "unconnected-(MTG7-Pad0)") (class "Default")
      (node (ref "MTG7") (pin "0") (pinfunction "0_0") (pintype "passive"))
    )
    (net (code "76") (name "unconnected-(MTG8-Pad0)") (class "Default")
      (node (ref "MTG8") (pin "0") (pinfunction "0_0") (pintype "passive"))
    )
    (net (code "77") (name "unconnected-(U5-PC9-Pad49)") (class "Default")
      (node (ref "U5") (pin "49") (pinfunction "PC9_49") (pintype "passive+no_connect"))
    )
    (net (code "78") (name "unconnected-(U5-PC10-Pad64)") (class "Default")
      (node (ref "U5") (pin "64") (pinfunction "PC10_64") (pintype "passive+no_connect"))
    )
    (net (code "79") (name "unconnected-(U5-PC11-Pad1)") (class "Default")
      (node (ref "U5") (pin "1") (pinfunction "PC11_1") (pintype "passive+no_connect"))
    )
    (net (code "80") (name "unconnected-(U5-PD9-Pad41)") (class "Default")
      (node (ref "U5") (pin "41") (pinfunction "PD9_41") (pintype "passive+no_connect"))
    )
  )
)
